# Sheet1.net
KiCad netlist of a schematic drawn in Altium Designer
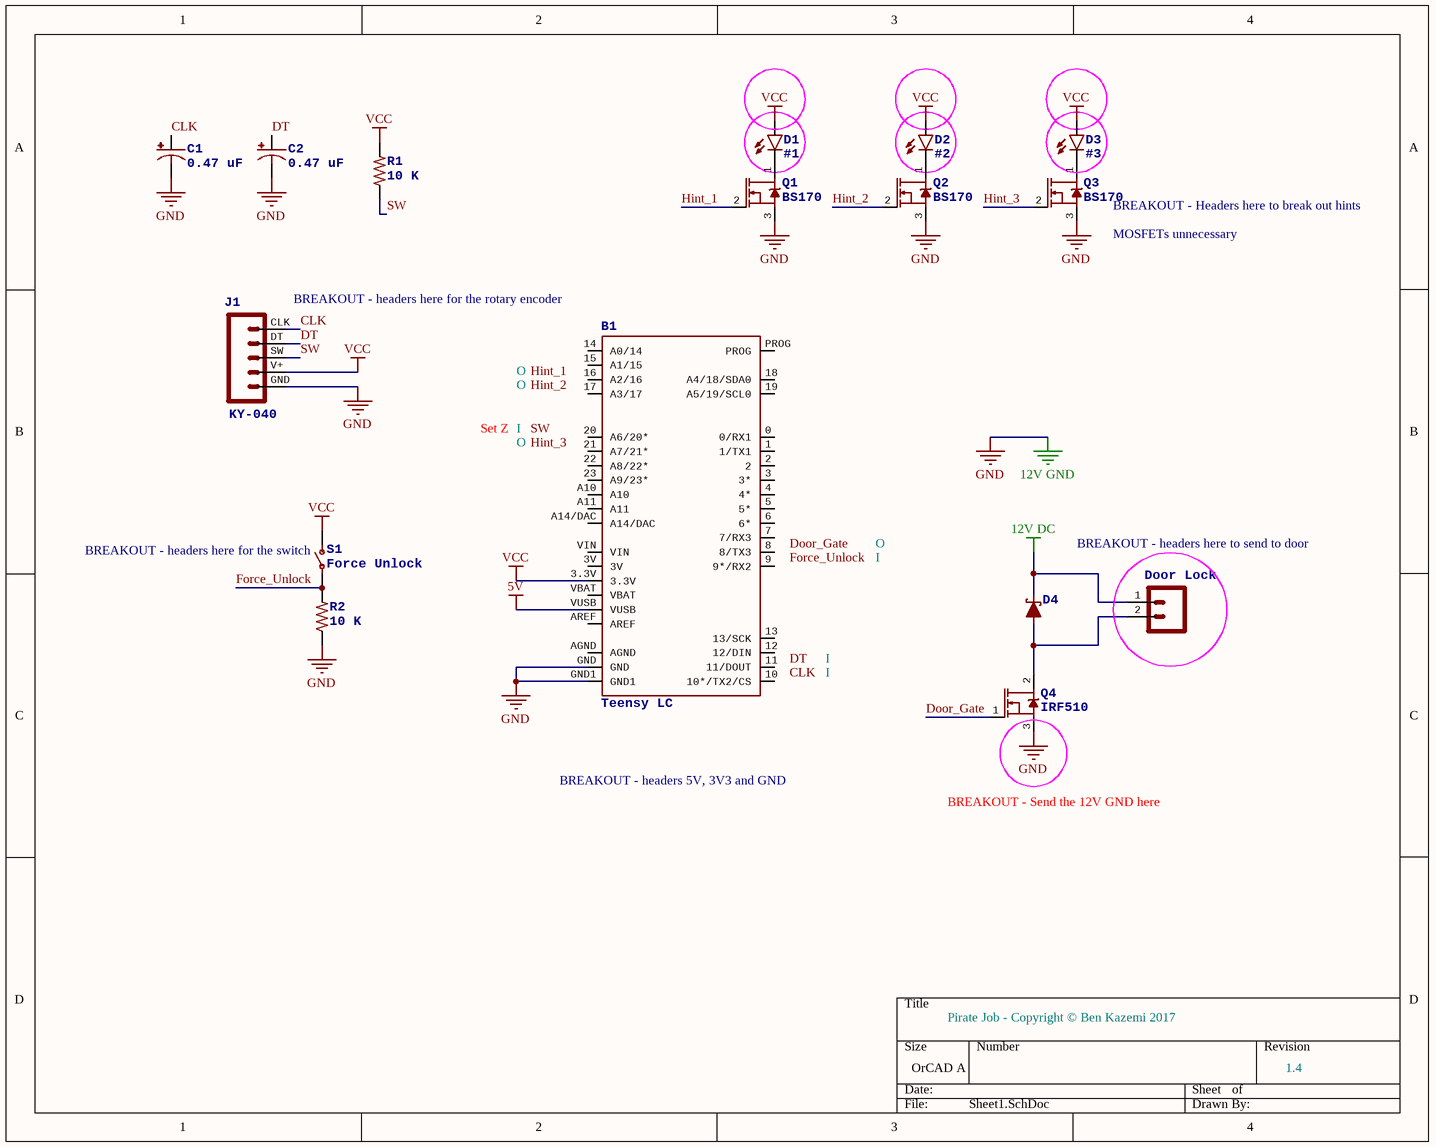
[diagram p0: Sheet1.SchDoc]

(export (version "E")
  (design (tool "Eeschema 10.0.6"))
  (components
    (comp (ref "B1")
      (value "Teensy LC")
      (footprint "TEENSY-3.1")
      (libsource (lib "SparkFun-Boards") (part "TEENSY-3.1SILK"))
    )
    (comp (ref "C1")
      (value "0.47 uF")
      (footprint "PANASONIC_D")
      (libsource (lib "SparkFun-Capacitors") (part "47UF-POLAR-PANASONIC_D-50V-20%"))
    )
    (comp (ref "C2")
      (value "0.47 uF")
      (footprint "PANASONIC_D")
      (libsource (lib "SparkFun-Capacitors") (part "47UF-POLAR-PANASONIC_D-50V-20%"))
    )
    (comp (ref "D1") (value "#1") (footprint "LED_5MM") (libsource (lib "SparkFun-LED") (part "LED5MM")))
    (comp (ref "D2") (value "#2") (footprint "LED_5MM") (libsource (lib "SparkFun-LED") (part "LED5MM")))
    (comp (ref "D3") (value "#3") (footprint "LED_5MM") (libsource (lib "SparkFun-LED") (part "LED5MM")))
    (comp (ref "D4")
      (value "~")
      (footprint "SOD-323")
      (libsource (lib "SparkFun-DiscreteSemi") (part "DIODE-SCHOTTKY-BAT20J"))
    )
    (comp (ref "Door Lock")
      (value "~")
      (footprint "1X02_LOCK")
      (libsource (lib "SparkFun-Connectors") (part "CONN_02LOCK"))
    )
    (comp (ref "J1")
      (value "KY-040")
      (footprint "1X05")
      (description "Rotary Encoder")
      (libsource (lib "SparkFun-Connectors") (part "CONN_05"))
    )
    (comp (ref "Q1")
      (value "BS170")
      (footprint "TO-92")
      (libsource (lib "SparkFun-DiscreteSemi") (part "MOSFET-NCH-FQP30N06L"))
    )
    (comp (ref "Q2")
      (value "BS170")
      (footprint "TO-92")
      (libsource (lib "SparkFun-DiscreteSemi") (part "MOSFET-NCH-FQP30N06L"))
    )
    (comp (ref "Q3")
      (value "BS170")
      (footprint "TO-92")
      (libsource (lib "SparkFun-DiscreteSemi") (part "MOSFET-NCH-FQP30N06L"))
    )
    (comp (ref "Q4")
      (value "IRF510")
      (footprint "TO220V")
      (libsource (lib "") (part "MOSFET-NCH-FQP30N06L_1"))
    )
    (comp (ref "R1")
      (value "10 K")
      (footprint "AXIAL-0.3")
      (libsource (lib "SparkFun-Resistors") (part "10KOHM-HORIZ-1/4W-5%"))
    )
    (comp (ref "R2")
      (value "10 K")
      (footprint "AXIAL-0.3")
      (libsource (lib "SparkFun-Resistors") (part "10KOHM-HORIZ-1/4W-5%"))
    )
    (comp (ref "S1")
      (value "Force Unlock")
      (footprint "SWITCH-SPST-VERTICAL")
      (libsource (lib "SparkFun-Retired") (part "SWITCH-SPST-2TV"))
    )
  )
  (nets
    (net (code "1") (name "/CLK") (class "Default")
      (node (ref "C1") (pin "+") (pinfunction "+_+") (pintype "passive"))
      (node (ref "J1") (pin "CLK") (pinfunction "5_CLK") (pintype "passive"))
    )
    (net (code "2") (name "/DT") (class "Default")
      (node (ref "C2") (pin "+") (pinfunction "+_+") (pintype "passive"))
      (node (ref "J1") (pin "DT") (pinfunction "4_DT") (pintype "passive"))
    )
    (net (code "3") (name "/Door_Gate") (class "Default")
      (node (ref "Q4") (pin "1") (pinfunction "G_1") (pintype "passive"))
    )
    (net (code "4") (name "/Force_Unlock") (class "Default")
      (node (ref "R2") (pin "P$2") (pinfunction "2_P$2") (pintype "passive"))
      (node (ref "S1") (pin "2") (pinfunction "P_2") (pintype "passive"))
    )
    (net (code "5") (name "/Hint_1") (class "Default")
      (node (ref "Q1") (pin "2") (pinfunction "G_2") (pintype "passive"))
    )
    (net (code "6") (name "/Hint_2") (class "Default")
      (node (ref "Q2") (pin "2") (pinfunction "G_2") (pintype "passive"))
    )
    (net (code "7") (name "/Hint_3") (class "Default")
      (node (ref "Q3") (pin "2") (pinfunction "G_2") (pintype "passive"))
    )
    (net (code "8") (name "/SW") (class "Default")
      (node (ref "J1") (pin "SW") (pinfunction "3_SW") (pintype "passive"))
      (node (ref "R1") (pin "P$1") (pinfunction "1_P$1") (pintype "passive"))
    )
    (net (code "9") (name "5V") (class "Default")
      (node (ref "B1") (pin "VUSB") (pinfunction "VUSB_VUSB") (pintype "power_in"))
    )
    (net (code "10") (name "12V DC") (class "Default")
      (node (ref "D4") (pin "C") (pinfunction "C_C") (pintype "passive"))
      (node (ref "Door Lock") (pin "1") (pinfunction "1_1") (pintype "passive"))
    )
    (net (code "11") (name "12V GND") (class "Default")
      (node (ref "B1") (pin "GND") (pinfunction "GND_GND") (pintype "power_in"))
      (node (ref "B1") (pin "GND1") (pinfunction "GND1_GND1") (pintype "power_in"))
      (node (ref "C1") (pin "-") (pinfunction "-_-") (pintype "passive"))
      (node (ref "C2") (pin "-") (pinfunction "-_-") (pintype "passive"))
      (node (ref "J1") (pin "GND") (pinfunction "1_GND") (pintype "passive"))
      (node (ref "Q1") (pin "3") (pinfunction "S_3") (pintype "passive"))
      (node (ref "Q2") (pin "3") (pinfunction "S_3") (pintype "passive"))
      (node (ref "Q3") (pin "3") (pinfunction "S_3") (pintype "passive"))
      (node (ref "Q4") (pin "3") (pinfunction "S_3") (pintype "passive"))
      (node (ref "R2") (pin "P$1") (pinfunction "1_P$1") (pintype "passive"))
    )
    (net (code "12") (name "Net-(D1-C)") (class "Default")
      (node (ref "D1") (pin "K") (pinfunction "C_K") (pintype "passive"))
      (node (ref "Q1") (pin "1") (pinfunction "D_1") (pintype "passive"))
    )
    (net (code "13") (name "Net-(D2-C)") (class "Default")
      (node (ref "D2") (pin "K") (pinfunction "C_K") (pintype "passive"))
      (node (ref "Q2") (pin "1") (pinfunction "D_1") (pintype "passive"))
    )
    (net (code "14") (name "Net-(D3-C)") (class "Default")
      (node (ref "D3") (pin "K") (pinfunction "C_K") (pintype "passive"))
      (node (ref "Q3") (pin "1") (pinfunction "D_1") (pintype "passive"))
    )
    (net (code "15") (name "Net-(Q4-D)") (class "Default")
      (node (ref "D4") (pin "A") (pinfunction "A_A") (pintype "passive"))
      (node (ref "Door Lock") (pin "2") (pinfunction "2_2") (pintype "passive"))
      (node (ref "Q4") (pin "2") (pinfunction "D_2") (pintype "passive"))
    )
    (net (code "16") (name "VCC") (class "Default")
      (node (ref "B1") (pin "3.3V") (pinfunction "3.3V_3.3V") (pintype "power_in"))
      (node (ref "D1") (pin "A") (pinfunction "A_A") (pintype "passive"))
      (node (ref "D2") (pin "A") (pinfunction "A_A") (pintype "passive"))
      (node (ref "D3") (pin "A") (pinfunction "A_A") (pintype "passive"))
      (node (ref "J1") (pin "V+") (pinfunction "2_V+") (pintype "passive"))
      (node (ref "R1") (pin "P$2") (pinfunction "2_P$2") (pintype "passive"))
      (node (ref "S1") (pin "1") (pinfunction "O_1") (pintype "passive"))
    )
    (net (code "17") (name "unconnected-(B1-0{slash}RX1-Pad0)") (class "Default")
      (node (ref "B1") (pin "0") (pinfunction "0/RX1_0") (pintype "passive"))
    )
    (net (code "18") (name "unconnected-(B1-1{slash}TX1-Pad1)") (class "Default")
      (node (ref "B1") (pin "1") (pinfunction "1/TX1_1") (pintype "passive"))
    )
    (net (code "19") (name "unconnected-(B1-3*-Pad3)") (class "Default")
      (node (ref "B1") (pin "3") (pinfunction "3*_3") (pintype "passive"))
    )
    (net (code "20") (name "unconnected-(B1-4*-Pad4)") (class "Default")
      (node (ref "B1") (pin "4") (pinfunction "4*_4") (pintype "passive"))
    )
    (net (code "21") (name "unconnected-(B1-5*-Pad5)") (class "Default")
      (node (ref "B1") (pin "5") (pinfunction "5*_5") (pintype "passive"))
    )
    (net (code "22") (name "unconnected-(B1-6*-Pad6)") (class "Default")
      (node (ref "B1") (pin "6") (pinfunction "6*_6") (pintype "passive"))
    )
    (net (code "23") (name "unconnected-(B1-7{slash}RX3-Pad7)") (class "Default")
      (node (ref "B1") (pin "7") (pinfunction "7/RX3_7") (pintype "passive"))
    )
    (net (code "24") (name "unconnected-(B1-8{slash}TX3-Pad8)") (class "Default")
      (node (ref "B1") (pin "8") (pinfunction "8/TX3_8") (pintype "passive"))
    )
    (net (code "25") (name "unconnected-(B1-9*{slash}RX2-Pad9)") (class "Default")
      (node (ref "B1") (pin "9") (pinfunction "9*/RX2_9") (pintype "passive"))
    )
    (net (code "26") (name "unconnected-(B1-10*{slash}TX2{slash}CS-Pad10)") (class "Default")
      (node (ref "B1") (pin "10") (pinfunction "10*/TX2/CS_10") (pintype "passive"))
    )
    (net (code "27") (name "unconnected-(B1-11{slash}DOUT-Pad11)") (class "Default")
      (node (ref "B1") (pin "11") (pinfunction "11/DOUT_11") (pintype "passive"))
    )
    (net (code "28") (name "unconnected-(B1-12{slash}DIN-Pad12)") (class "Default")
      (node (ref "B1") (pin "12") (pinfunction "12/DIN_12") (pintype "passive"))
    )
    (net (code "29") (name "unconnected-(B1-13{slash}SCK-Pad13)") (class "Default")
      (node (ref "B1") (pin "13") (pinfunction "13/SCK_13") (pintype "passive"))
    )
    (net (code "30") (name "unconnected-(B1-A0{slash}14-Pad14)") (class "Default")
      (node (ref "B1") (pin "14") (pinfunction "A0/14_14") (pintype "passive"))
    )
    (net (code "31") (name "unconnected-(B1-A1{slash}15-Pad15)") (class "Default")
      (node (ref "B1") (pin "15") (pinfunction "A1/15_15") (pintype "passive"))
    )
    (net (code "32") (name "unconnected-(B1-A2{slash}16-Pad16)") (class "Default")
      (node (ref "B1") (pin "16") (pinfunction "A2/16_16") (pintype "passive"))
    )
    (net (code "33") (name "unconnected-(B1-A3{slash}17-Pad17)") (class "Default")
      (node (ref "B1") (pin "17") (pinfunction "A3/17_17") (pintype "passive"))
    )
    (net (code "34") (name "unconnected-(B1-A4{slash}18{slash}SDA0-Pad18)") (class "Default")
      (node (ref "B1") (pin "18") (pinfunction "A4/18/SDA0_18") (pintype "passive"))
    )
    (net (code "35") (name "unconnected-(B1-A5{slash}19{slash}SCL0-Pad19)") (class "Default")
      (node (ref "B1") (pin "19") (pinfunction "A5/19/SCL0_19") (pintype "passive"))
    )
    (net (code "36") (name "unconnected-(B1-A6{slash}20*-Pad20)") (class "Default")
      (node (ref "B1") (pin "20") (pinfunction "A6/20*_20") (pintype "passive"))
    )
    (net (code "37") (name "unconnected-(B1-A7{slash}21*-Pad21)") (class "Default")
      (node (ref "B1") (pin "21") (pinfunction "A7/21*_21") (pintype "passive"))
    )
    (net (code "38") (name "unconnected-(B1-A8{slash}22*-Pad22)") (class "Default")
      (node (ref "B1") (pin "22") (pinfunction "A8/22*_22") (pintype "passive"))
    )
    (net (code "39") (name "unconnected-(B1-A9{slash}23*-Pad23)") (class "Default")
      (node (ref "B1") (pin "23") (pinfunction "A9/23*_23") (pintype "passive"))
    )
    (net (code "40") (name "unconnected-(B1-Pad2)") (class "Default")
      (node (ref "B1") (pin "2") (pinfunction "2_2") (pintype "passive"))
    )
    (net (code "41") (name "unconnected-(B1-Pad3V)") (class "Default")
      (node (ref "B1") (pin "3V") (pinfunction "3V_3V") (pintype "power_in"))
    )
    (net (code "42") (name "unconnected-(B1-PadA10)") (class "Default")
      (node (ref "B1") (pin "A10") (pinfunction "A10_A10") (pintype "passive"))
    )
    (net (code "43") (name "unconnected-(B1-PadA11)") (class "Default")
      (node (ref "B1") (pin "A11") (pinfunction "A11_A11") (pintype "passive"))
    )
    (net (code "44") (name "unconnected-(B1-PadA14{slash}DAC)") (class "Default")
      (node (ref "B1") (pin "A14/DAC") (pinfunction "A14/DAC_A14/DAC") (pintype "passive"))
    )
    (net (code "45") (name "unconnected-(B1-PadAGND)") (class "Default")
      (node (ref "B1") (pin "AGND") (pinfunction "AGND_AGND") (pintype "power_in"))
    )
    (net (code "46") (name "unconnected-(B1-PadAREF)") (class "Default")
      (node (ref "B1") (pin "AREF") (pinfunction "AREF_AREF") (pintype "passive"))
    )
    (net (code "47") (name "unconnected-(B1-PadPROG)") (class "Default")
      (node (ref "B1") (pin "PROG") (pinfunction "PROG_PROG") (pintype "passive"))
    )
    (net (code "48") (name "unconnected-(B1-PadVBAT)") (class "Default")
      (node (ref "B1") (pin "VBAT") (pinfunction "VBAT_VBAT") (pintype "power_in"))
    )
    (net (code "49") (name "unconnected-(B1-PadVIN)") (class "Default")
      (node (ref "B1") (pin "VIN") (pinfunction "VIN_VIN") (pintype "power_in"))
    )
  )
)
